# x8.net
KiCad netlist of a schematic drawn in EAGLE
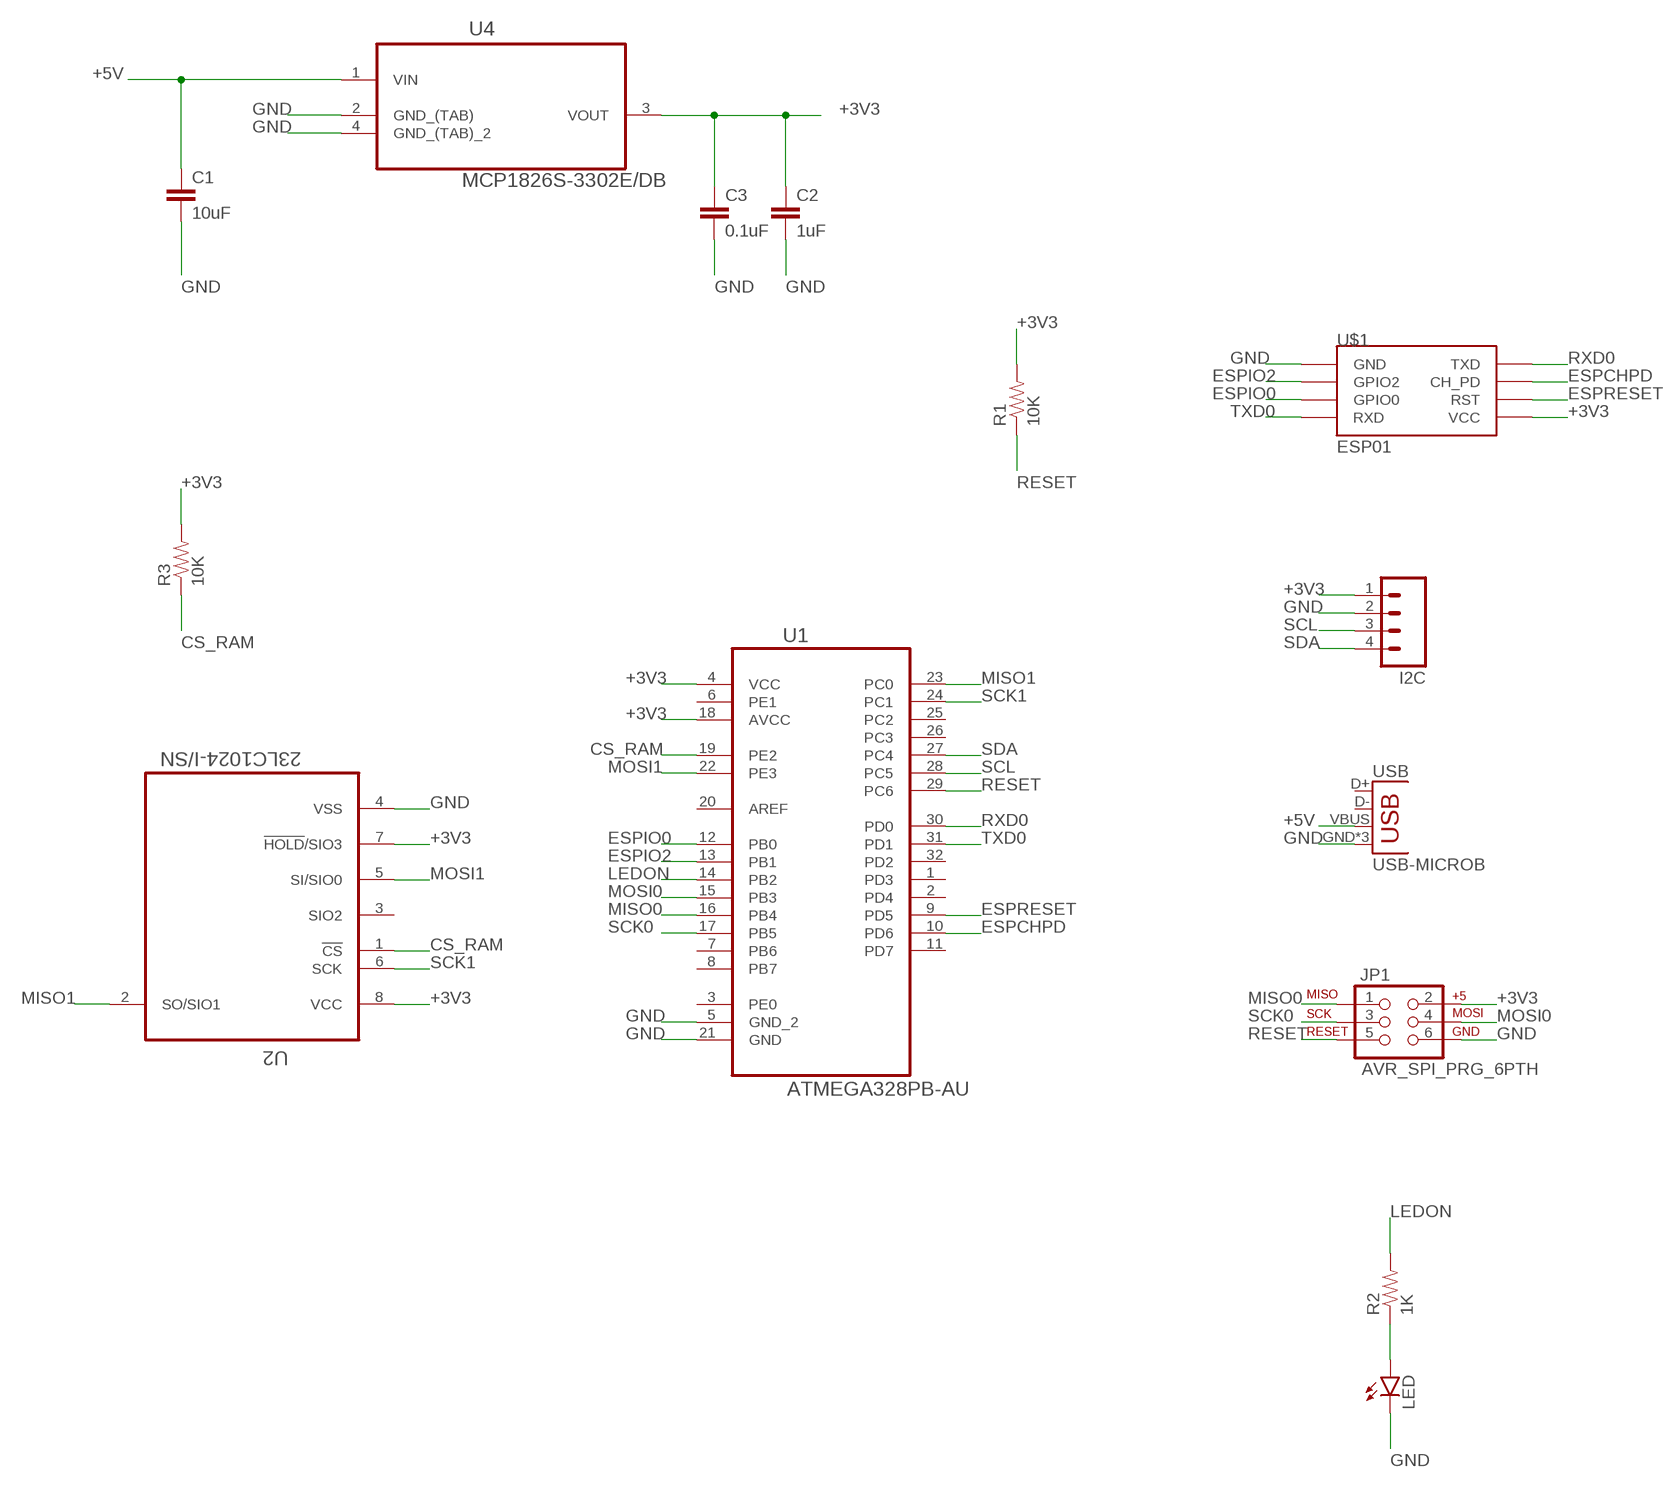
[diagram p0: schematic, sheet 1]

(export (version "E")
  (design (tool "Eeschema 10.0.6"))
  (components
    (comp (ref "C1")
      (value "10uF")
      (footprint "eagle-import:0402-CAP")
      (libsource (lib "eagle-import") (part "CAP0402-CAP"))
    )
    (comp (ref "C2")
      (value "1uF")
      (footprint "eagle-import:0402-CAP")
      (libsource (lib "eagle-import") (part "CAP0402-CAP"))
    )
    (comp (ref "C3")
      (value "0.1uF")
      (footprint "eagle-import:0402-CAP")
      (libsource (lib "eagle-import") (part "CAP0402-CAP"))
    )
    (comp (ref "I2C")
      (value "M04PTH")
      (footprint "eagle-import:1X04")
      (libsource (lib "eagle-import") (part "M04PTH"))
    )
    (comp (ref "JP1")
      (value "AVR_SPI_PRG_6PTH")
      (footprint "eagle-import:2X3")
      (libsource (lib "eagle-import") (part "AVR_SPI_PRG_6PTH"))
    )
    (comp (ref "LED")
      (value "LED0603")
      (footprint "eagle-import:LED-0603")
      (libsource (lib "eagle-import") (part "LED0603"))
    )
    (comp (ref "R1")
      (value "10K")
      (footprint "eagle-import:0402-RES")
      (libsource (lib "eagle-import") (part "RESISTOR0402"))
    )
    (comp (ref "R2")
      (value "1K")
      (footprint "eagle-import:0402-RES")
      (libsource (lib "eagle-import") (part "RESISTOR0402"))
    )
    (comp (ref "R3")
      (value "10K")
      (footprint "eagle-import:0402-RES")
      (libsource (lib "eagle-import") (part "RESISTOR0402"))
    )
    (comp (ref "U$1")
      (value "ESP01")
      (footprint "eagle-import:ESP01")
      (libsource (lib "eagle-import") (part "ESP01"))
    )
    (comp (ref "U1")
      (value "ATMEGA328PB-AU")
      (footprint "eagle-import:QFP80P900X900X120-32N")
      (fields (field (name "MPN") "ATMEGA328P-AU"))
      (libsource (lib "eagle-import") (part "ATMEGA328PB-AU"))
    )
    (comp (ref "U2")
      (value "23LC1024-I/SN")
      (footprint "eagle-import:SOIC127P600X175-8N")
      (libsource (lib "eagle-import") (part "23LC1024-I/SN"))
    )
    (comp (ref "U4")
      (value "MCP1826S-3302E/DB")
      (footprint "eagle-import:SOT230P700X180-4N")
      (libsource (lib "eagle-import") (part "MCP1826S-3302E/DB"))
    )
    (comp (ref "USB")
      (value "USB-MICROB")
      (footprint "eagle-import:USB-MICROB")
      (libsource (lib "eagle-import") (part "USB-MICROB"))
    )
  )
  (nets
    (net (code "1") (name "/+3V3") (class "Default")
      (node (ref "C2") (pin "1") (pinfunction "1_1") (pintype "passive"))
      (node (ref "C3") (pin "1") (pinfunction "1_1") (pintype "passive"))
      (node (ref "I2C") (pin "1") (pinfunction "1_1") (pintype "passive"))
      (node (ref "JP1") (pin "2") (pinfunction "2_2") (pintype "passive"))
      (node (ref "R1") (pin "2") (pinfunction "2_2") (pintype "passive"))
      (node (ref "R3") (pin "2") (pinfunction "2_2") (pintype "passive"))
      (node (ref "U$1") (pin "VCC") (pinfunction "VCC_VCC") (pintype "bidirectional"))
      (node (ref "U1") (pin "18") (pinfunction "AVCC_18") (pintype "power_in"))
      (node (ref "U1") (pin "4") (pinfunction "VCC_4") (pintype "power_in"))
      (node (ref "U2") (pin "7") (pinfunction "~{HOLD}/SIO3_7") (pintype "passive"))
      (node (ref "U2") (pin "8") (pinfunction "VCC_8") (pintype "power_in"))
      (node (ref "U4") (pin "3") (pinfunction "VOUT_3") (pintype "output"))
    )
    (net (code "2") (name "/+5V") (class "Default")
      (node (ref "C1") (pin "1") (pinfunction "1_1") (pintype "passive"))
      (node (ref "U4") (pin "1") (pinfunction "VIN_1") (pintype "input"))
      (node (ref "USB") (pin "VBUS") (pinfunction "VBUS_VBUS") (pintype "bidirectional"))
    )
    (net (code "3") (name "/CS_RAM") (class "Default")
      (node (ref "R3") (pin "1") (pinfunction "1_1") (pintype "passive"))
      (node (ref "U1") (pin "19") (pinfunction "PE2_19") (pintype "bidirectional"))
      (node (ref "U2") (pin "1") (pinfunction "~{CS}_1") (pintype "input"))
    )
    (net (code "4") (name "/ESPCHPD") (class "Default")
      (node (ref "U$1") (pin "CH_PD") (pinfunction "CH_PD_CH_PD") (pintype "bidirectional"))
      (node (ref "U1") (pin "10") (pinfunction "PD6_10") (pintype "bidirectional"))
    )
    (net (code "5") (name "/ESPIO0") (class "Default")
      (node (ref "U$1") (pin "GPIO0") (pinfunction "GPIO0_GPIO0") (pintype "bidirectional"))
      (node (ref "U1") (pin "12") (pinfunction "PB0_12") (pintype "bidirectional"))
    )
    (net (code "6") (name "/ESPIO2") (class "Default")
      (node (ref "U$1") (pin "GPIO2") (pinfunction "GPIO2_GPIO2") (pintype "bidirectional"))
      (node (ref "U1") (pin "13") (pinfunction "PB1_13") (pintype "bidirectional"))
    )
    (net (code "7") (name "/ESPRESET") (class "Default")
      (node (ref "U$1") (pin "RST") (pinfunction "RST_RST") (pintype "bidirectional"))
      (node (ref "U1") (pin "9") (pinfunction "PD5_9") (pintype "bidirectional"))
    )
    (net (code "8") (name "/GND") (class "Default")
      (node (ref "C1") (pin "2") (pinfunction "2_2") (pintype "passive"))
      (node (ref "C2") (pin "2") (pinfunction "2_2") (pintype "passive"))
      (node (ref "C3") (pin "2") (pinfunction "2_2") (pintype "passive"))
      (node (ref "I2C") (pin "2") (pinfunction "2_2") (pintype "passive"))
      (node (ref "JP1") (pin "6") (pinfunction "6_6") (pintype "passive"))
      (node (ref "LED") (pin "C") (pinfunction "C_C") (pintype "passive"))
      (node (ref "U$1") (pin "GND") (pinfunction "GND_GND") (pintype "bidirectional"))
      (node (ref "U1") (pin "21") (pinfunction "GND_21") (pintype "passive"))
      (node (ref "U1") (pin "5") (pinfunction "GND_2_5") (pintype "passive"))
      (node (ref "U2") (pin "4") (pinfunction "VSS_4") (pintype "passive"))
      (node (ref "U4") (pin "2") (pinfunction "GND_(TAB)_2") (pintype "passive"))
      (node (ref "U4") (pin "4") (pinfunction "GND_(TAB)_2_4") (pintype "passive"))
      (node (ref "USB") (pin "GND") (pinfunction "GND_GND") (pintype "bidirectional"))
      (node (ref "USB") (pin "MT1") (pinfunction "GND_MT1") (pintype "bidirectional"))
      (node (ref "USB") (pin "MT2") (pinfunction "GND_MT2") (pintype "bidirectional"))
    )
    (net (code "9") (name "/LEDON") (class "Default")
      (node (ref "R2") (pin "2") (pinfunction "2_2") (pintype "passive"))
      (node (ref "U1") (pin "14") (pinfunction "PB2_14") (pintype "bidirectional"))
    )
    (net (code "10") (name "/MISO0") (class "Default")
      (node (ref "JP1") (pin "1") (pinfunction "1_1") (pintype "passive"))
      (node (ref "U1") (pin "16") (pinfunction "PB4_16") (pintype "bidirectional"))
    )
    (net (code "11") (name "/MISO1") (class "Default")
      (node (ref "U1") (pin "23") (pinfunction "PC0_23") (pintype "bidirectional"))
      (node (ref "U2") (pin "2") (pinfunction "SO/SIO1_2") (pintype "output"))
    )
    (net (code "12") (name "/MOSI0") (class "Default")
      (node (ref "JP1") (pin "4") (pinfunction "4_4") (pintype "passive"))
      (node (ref "U1") (pin "15") (pinfunction "PB3_15") (pintype "bidirectional"))
    )
    (net (code "13") (name "/MOSI1") (class "Default")
      (node (ref "U1") (pin "22") (pinfunction "PE3_22") (pintype "bidirectional"))
      (node (ref "U2") (pin "5") (pinfunction "SI/SIO0_5") (pintype "input"))
    )
    (net (code "14") (name "/RESET") (class "Default")
      (node (ref "JP1") (pin "5") (pinfunction "5_5") (pintype "passive"))
      (node (ref "R1") (pin "1") (pinfunction "1_1") (pintype "passive"))
      (node (ref "U1") (pin "29") (pinfunction "PC6_29") (pintype "bidirectional"))
    )
    (net (code "15") (name "/RXD0") (class "Default")
      (node (ref "U$1") (pin "TX") (pinfunction "TXD_TX") (pintype "bidirectional"))
      (node (ref "U1") (pin "30") (pinfunction "PD0_30") (pintype "bidirectional"))
    )
    (net (code "16") (name "/SCK0") (class "Default")
      (node (ref "JP1") (pin "3") (pinfunction "3_3") (pintype "passive"))
      (node (ref "U1") (pin "17") (pinfunction "PB5_17") (pintype "bidirectional"))
    )
    (net (code "17") (name "/SCK1") (class "Default")
      (node (ref "U1") (pin "24") (pinfunction "PC1_24") (pintype "bidirectional"))
      (node (ref "U2") (pin "6") (pinfunction "SCK_6") (pintype "input"))
    )
    (net (code "18") (name "/SCL") (class "Default")
      (node (ref "I2C") (pin "3") (pinfunction "3_3") (pintype "passive"))
      (node (ref "U1") (pin "28") (pinfunction "PC5_28") (pintype "bidirectional"))
    )
    (net (code "19") (name "/SDA") (class "Default")
      (node (ref "I2C") (pin "4") (pinfunction "4_4") (pintype "passive"))
      (node (ref "U1") (pin "27") (pinfunction "PC4_27") (pintype "bidirectional"))
    )
    (net (code "20") (name "/TXD0") (class "Default")
      (node (ref "U$1") (pin "RX") (pinfunction "RXD_RX") (pintype "bidirectional"))
      (node (ref "U1") (pin "31") (pinfunction "PD1_31") (pintype "bidirectional"))
    )
    (net (code "21") (name "Net-(LED-PadA)") (class "Default")
      (node (ref "LED") (pin "A") (pinfunction "A_A") (pintype "passive"))
      (node (ref "R2") (pin "1") (pinfunction "1_1") (pintype "passive"))
    )
    (net (code "22") (name "unconnected-(U1-AREF-Pad20)") (class "Default")
      (node (ref "U1") (pin "20") (pinfunction "AREF_20") (pintype "input"))
    )
    (net (code "23") (name "unconnected-(U1-PB6-Pad7)") (class "Default")
      (node (ref "U1") (pin "7") (pinfunction "PB6_7") (pintype "bidirectional"))
    )
    (net (code "24") (name "unconnected-(U1-PB7-Pad8)") (class "Default")
      (node (ref "U1") (pin "8") (pinfunction "PB7_8") (pintype "bidirectional"))
    )
    (net (code "25") (name "unconnected-(U1-PC2-Pad25)") (class "Default")
      (node (ref "U1") (pin "25") (pinfunction "PC2_25") (pintype "bidirectional"))
    )
    (net (code "26") (name "unconnected-(U1-PC3-Pad26)") (class "Default")
      (node (ref "U1") (pin "26") (pinfunction "PC3_26") (pintype "bidirectional"))
    )
    (net (code "27") (name "unconnected-(U1-PD2-Pad32)") (class "Default")
      (node (ref "U1") (pin "32") (pinfunction "PD2_32") (pintype "bidirectional"))
    )
    (net (code "28") (name "unconnected-(U1-PD3-Pad1)") (class "Default")
      (node (ref "U1") (pin "1") (pinfunction "PD3_1") (pintype "bidirectional"))
    )
    (net (code "29") (name "unconnected-(U1-PD4-Pad2)") (class "Default")
      (node (ref "U1") (pin "2") (pinfunction "PD4_2") (pintype "bidirectional"))
    )
    (net (code "30") (name "unconnected-(U1-PD7-Pad11)") (class "Default")
      (node (ref "U1") (pin "11") (pinfunction "PD7_11") (pintype "bidirectional"))
    )
    (net (code "31") (name "unconnected-(U1-PE0-Pad3)") (class "Default")
      (node (ref "U1") (pin "3") (pinfunction "PE0_3") (pintype "bidirectional"))
    )
    (net (code "32") (name "unconnected-(U1-PE1-Pad6)") (class "Default")
      (node (ref "U1") (pin "6") (pinfunction "PE1_6") (pintype "bidirectional"))
    )
    (net (code "33") (name "unconnected-(U2-SIO2-Pad3)") (class "Default")
      (node (ref "U2") (pin "3") (pinfunction "SIO2_3") (pintype "passive"))
    )
    (net (code "34") (name "unconnected-(USB-PadD+)") (class "Default")
      (node (ref "USB") (pin "D+") (pinfunction "D+_D+") (pintype "bidirectional"))
    )
    (net (code "35") (name "unconnected-(USB-PadD-)") (class "Default")
      (node (ref "USB") (pin "D-") (pinfunction "D-_D-") (pintype "bidirectional"))
    )
  )
)
